# NRF24L01.net
KiCad netlist of a schematic drawn in Altium Designer
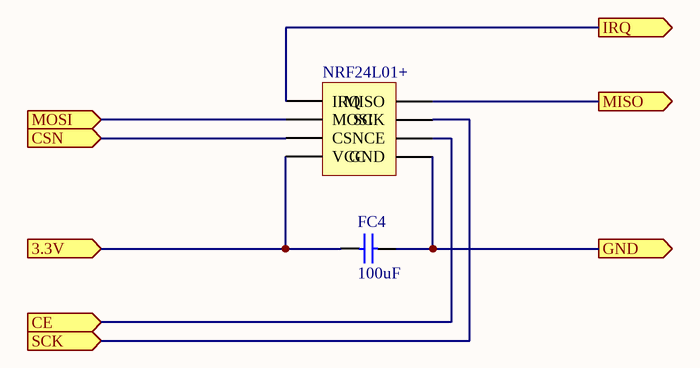
[diagram p0: NRF24L01+.SchDoc]

(export (version "E")
  (design (tool "Eeschema 10.0.6"))
  (components
    (comp (ref "FC4")
      (value "100uF")
      (footprint "RAD-0.3")
      (description "Capacitor")
      (fields (field (name "PUBLISHER") "Altium Limited"))
      (libsource (lib "Miscellaneous Devices") (part "Cap"))
    )
    (comp (ref "NRF24L01+")
      (value "nRF24L01+")
      (footprint "HDR2X4")
      (description "Header, 4-Pin, Dual row")
      (fields (field (name "PUBLISHER") "Altium Limited"))
      (libsource (lib "Miscellaneous Connectors") (part "Header 4X2"))
    )
  )
  (nets
    (net (code "1") (name "/3.3V") (class "Default")
      (node (ref "FC4") (pin "1") (pinfunction "1_1") (pintype "passive"))
      (node (ref "NRF24L01+") (pin "2") (pinfunction "VCC_2") (pintype "passive"))
    )
    (net (code "2") (name "/CE") (class "Default")
      (node (ref "NRF24L01+") (pin "3") (pinfunction "CE_3") (pintype "passive"))
    )
    (net (code "3") (name "/CSN") (class "Default")
      (node (ref "NRF24L01+") (pin "4") (pinfunction "CSN_4") (pintype "passive"))
    )
    (net (code "4") (name "/GND") (class "Default")
      (node (ref "FC4") (pin "2") (pinfunction "2_2") (pintype "passive"))
      (node (ref "NRF24L01+") (pin "1") (pinfunction "GND_1") (pintype "passive"))
    )
    (net (code "5") (name "/IRQ") (class "Default")
      (node (ref "NRF24L01+") (pin "8") (pinfunction "IRQ_8") (pintype "passive"))
    )
    (net (code "6") (name "/MISO") (class "Default")
      (node (ref "NRF24L01+") (pin "7") (pinfunction "MISO_7") (pintype "passive"))
    )
    (net (code "7") (name "/MOSI") (class "Default")
      (node (ref "NRF24L01+") (pin "6") (pinfunction "MOSI_6") (pintype "passive"))
    )
    (net (code "8") (name "/SCK") (class "Default")
      (node (ref "NRF24L01+") (pin "5") (pinfunction "SCK_5") (pintype "passive"))
    )
  )
)
